# USBPowerWallSocket.net
KiCad netlist of a schematic drawn in EAGLE
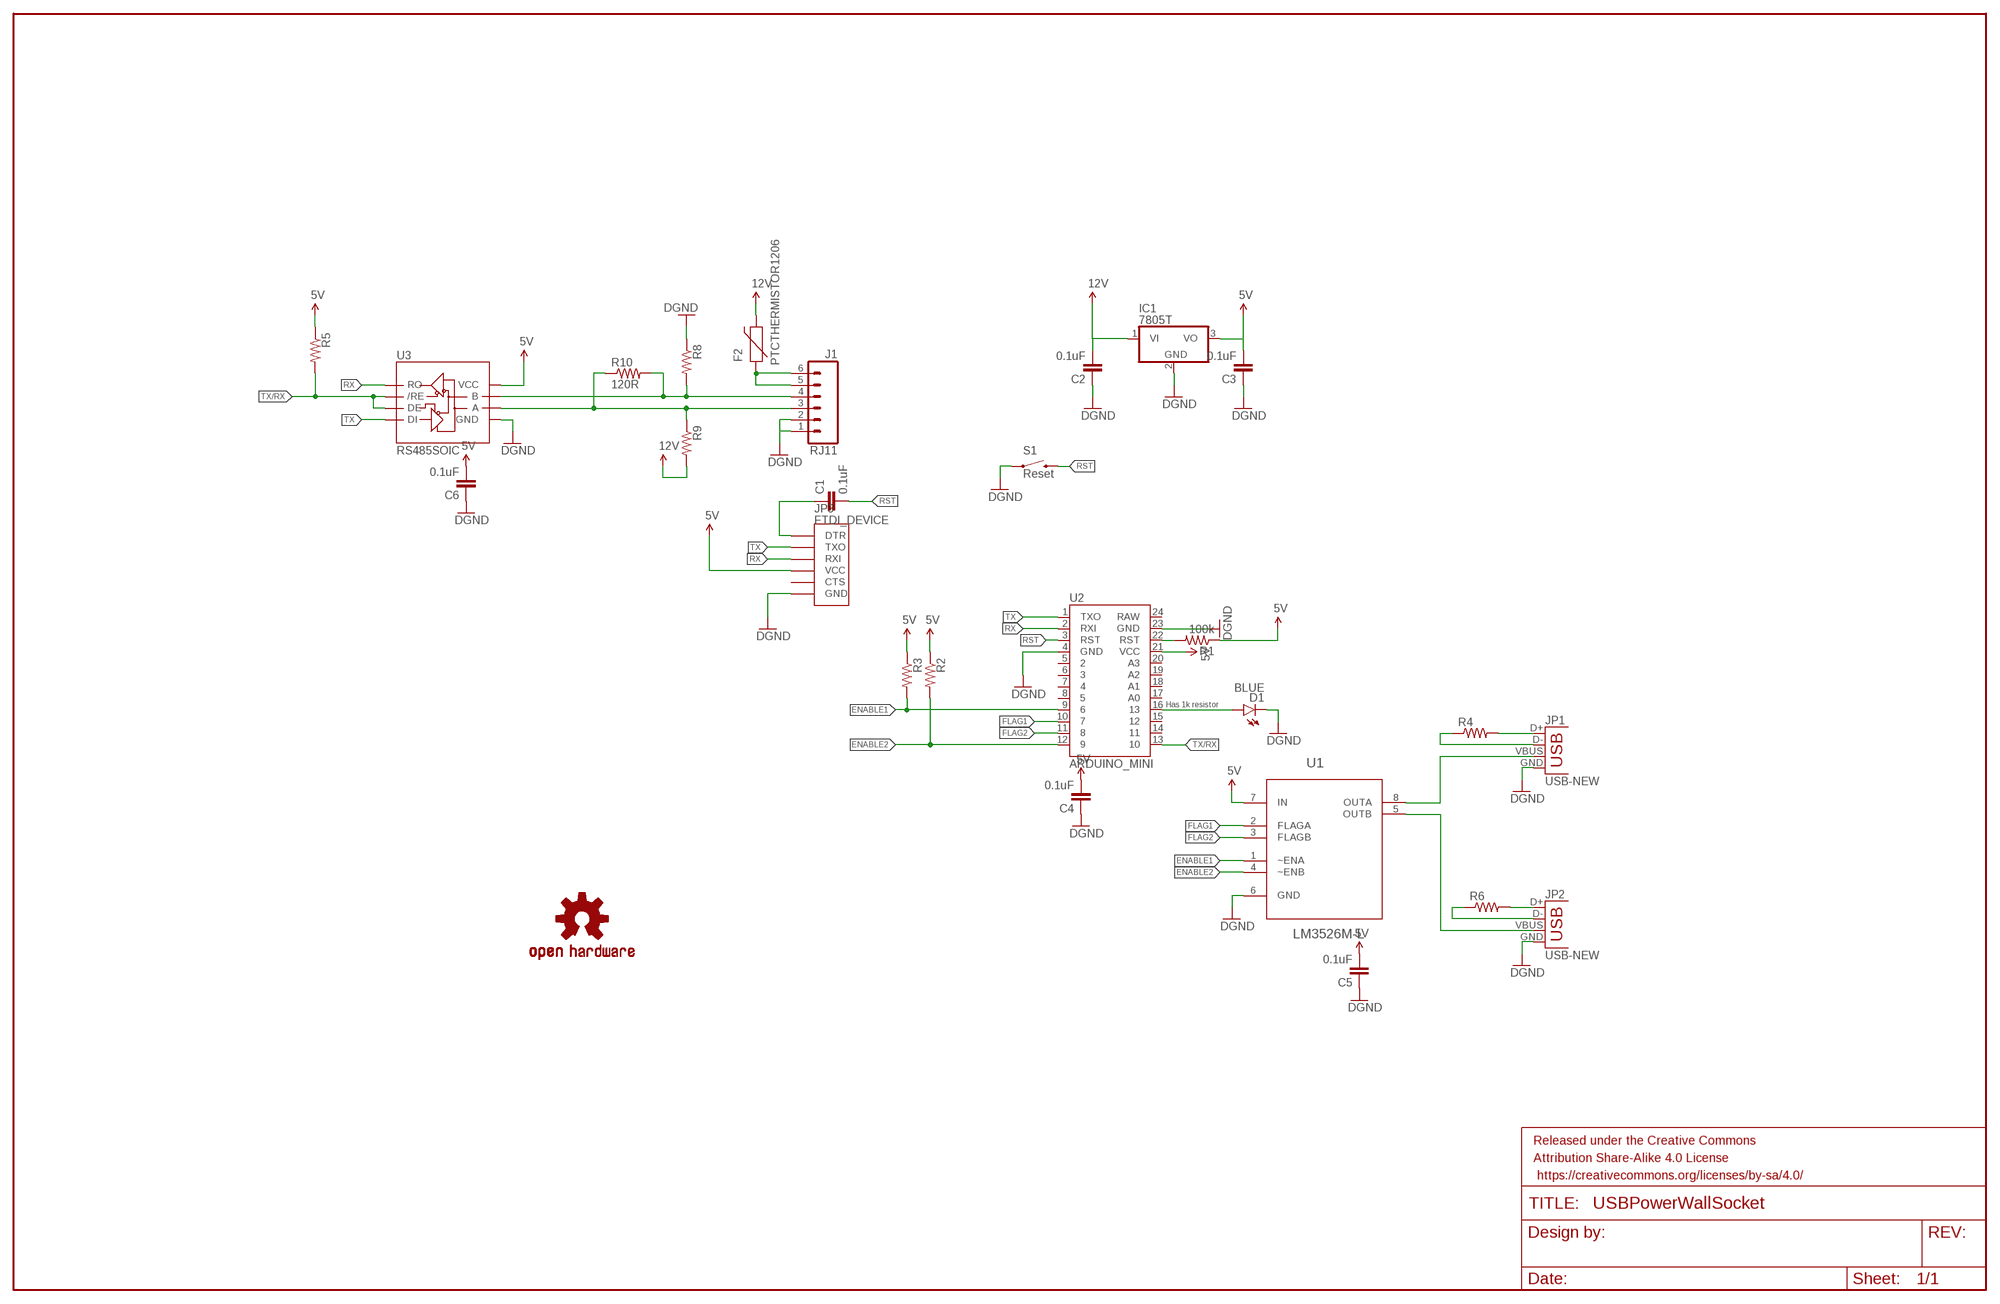
[diagram p0: schematic, sheet 1]

(export (version "E")
  (design (tool "Eeschema 10.0.6"))
  (components
    (comp (ref "C1")
      (value "0.1uF")
      (footprint "eagle-import:0805")
      (libsource (lib "eagle-import") (part "CAP0805"))
    )
    (comp (ref "C2")
      (value "0.1uF")
      (footprint "eagle-import:0805")
      (libsource (lib "eagle-import") (part "CAP0805"))
    )
    (comp (ref "C3")
      (value "0.1uF")
      (footprint "eagle-import:0805")
      (libsource (lib "eagle-import") (part "CAP0805"))
    )
    (comp (ref "C4")
      (value "0.1uF")
      (footprint "eagle-import:0805")
      (libsource (lib "eagle-import") (part "CAP0805"))
    )
    (comp (ref "C5")
      (value "0.1uF")
      (footprint "eagle-import:0805")
      (libsource (lib "eagle-import") (part "CAP0805"))
    )
    (comp (ref "C6")
      (value "0.1uF")
      (footprint "eagle-import:0805")
      (libsource (lib "eagle-import") (part "CAP0805"))
    )
    (comp (ref "D1")
      (value "BLUE")
      (footprint "eagle-import:LED-1206")
      (libsource (lib "eagle-import") (part "LED-BLUE1206"))
    )
    (comp (ref "F2")
      (value "PTCTHERMISTOR1206")
      (footprint "eagle-import:PTC-1206")
      (libsource (lib "eagle-import") (part "PTCTHERMISTOR1206"))
    )
    (comp (ref "FRAME1")
      (value "FRAME-LEDGER")
      (footprint "eagle-import:CREATIVE_COMMONS")
      (libsource (lib "eagle-import") (part "FRAME-LEDGER"))
    )
    (comp (ref "IC1")
      (value "7805T")
      (footprint "eagle-import:TO220H")
      (libsource (lib "eagle-import") (part "78T05"))
    )
    (comp (ref "J1")
      (value "RJ11")
      (footprint "eagle-import:RJ11-6")
      (libsource (lib "eagle-import") (part "RJ11-6PTH"))
    )
    (comp (ref "JP1")
      (value "USB-NEW")
      (footprint "eagle-import:USB-A-VERTICAL")
      (libsource (lib "eagle-import") (part "USB-NEW"))
    )
    (comp (ref "JP2")
      (value "USB-NEW")
      (footprint "eagle-import:USB-A-VERTICAL")
      (libsource (lib "eagle-import") (part "USB-NEW"))
    )
    (comp (ref "JP3")
      (value "FTDI_DEVICE")
      (footprint "eagle-import:FTDI_DEVICE_SIDE")
      (libsource (lib "eagle-import") (part "FTDI_DEVICE"))
    )
    (comp (ref "LOGO1")
      (value "OSHW-LOGOM")
      (footprint "eagle-import:OSHW-LOGO-M")
      (libsource (lib "eagle-import") (part "OSHW-LOGOM"))
    )
    (comp (ref "R1")
      (value "100k")
      (footprint "eagle-import:0805")
      (libsource (lib "eagle-import") (part "RESISTOR0805-RES"))
    )
    (comp (ref "R2")
      (value "RESISTOR0805-RES")
      (footprint "eagle-import:0805")
      (libsource (lib "eagle-import") (part "RESISTOR0805-RES"))
    )
    (comp (ref "R3")
      (value "RESISTOR0805-RES")
      (footprint "eagle-import:0805")
      (libsource (lib "eagle-import") (part "RESISTOR0805-RES"))
    )
    (comp (ref "R4")
      (value "RESISTOR0805-RES")
      (footprint "eagle-import:0805")
      (libsource (lib "eagle-import") (part "RESISTOR0805-RES"))
    )
    (comp (ref "R5")
      (value "RESISTOR0805-RES")
      (footprint "eagle-import:0805")
      (libsource (lib "eagle-import") (part "RESISTOR0805-RES"))
    )
    (comp (ref "R6")
      (value "RESISTOR0805-RES")
      (footprint "eagle-import:0805")
      (libsource (lib "eagle-import") (part "RESISTOR0805-RES"))
    )
    (comp (ref "R8")
      (value "RESISTOR0805-RES")
      (footprint "eagle-import:0805")
      (libsource (lib "eagle-import") (part "RESISTOR0805-RES"))
    )
    (comp (ref "R9")
      (value "RESISTOR0805-RES")
      (footprint "eagle-import:0805")
      (libsource (lib "eagle-import") (part "RESISTOR0805-RES"))
    )
    (comp (ref "R10")
      (value "120R")
      (footprint "eagle-import:0805")
      (libsource (lib "eagle-import") (part "RESISTOR0805-RES"))
    )
    (comp (ref "S1")
      (value "Reset")
      (footprint "eagle-import:TACTILE-PTH")
      (libsource (lib "eagle-import") (part "SWITCH-MOMENTARY-2PTH"))
    )
    (comp (ref "U1")
      (value "LM3526M-L")
      (footprint "eagle-import:SOIC127P640X175-8N")
      (libsource (lib "eagle-import") (part "LM3526M-L"))
    )
    (comp (ref "U2")
      (value "ARDUINO_MINI")
      (footprint "eagle-import:ARDUINO_MINI")
      (libsource (lib "eagle-import") (part "ARDUINO_MINI"))
    )
    (comp (ref "U3")
      (value "RS485SOIC")
      (footprint "eagle-import:SO08")
      (libsource (lib "eagle-import") (part "RS485SOIC"))
    )
  )
  (nets
    (net (code "1") (name "5V") (class "Default")
      (node (ref "C3") (pin "2") (pinfunction "2_2") (pintype "passive"))
      (node (ref "C4") (pin "2") (pinfunction "2_2") (pintype "passive"))
      (node (ref "C5") (pin "2") (pinfunction "2_2") (pintype "passive"))
      (node (ref "C6") (pin "2") (pinfunction "2_2") (pintype "passive"))
      (node (ref "IC1") (pin "3") (pinfunction "VO_3") (pintype "passive"))
      (node (ref "JP3") (pin "P$4") (pinfunction "VCC_P$4") (pintype "bidirectional"))
      (node (ref "R1") (pin "1") (pinfunction "1_1") (pintype "passive"))
      (node (ref "R2") (pin "1") (pinfunction "1_1") (pintype "passive"))
      (node (ref "R3") (pin "1") (pinfunction "1_1") (pintype "passive"))
      (node (ref "R5") (pin "1") (pinfunction "1_1") (pintype "passive"))
      (node (ref "U1") (pin "7") (pinfunction "IN_7") (pintype "power_in"))
      (node (ref "U2") (pin "21") (pinfunction "VCC_21") (pintype "bidirectional"))
      (node (ref "U3") (pin "8") (pinfunction "VCC_8") (pintype "bidirectional"))
    )
    (net (code "2") (name "12V") (class "Default")
      (node (ref "C2") (pin "2") (pinfunction "2_2") (pintype "passive"))
      (node (ref "F2") (pin "2") (pinfunction "2_2") (pintype "bidirectional"))
      (node (ref "IC1") (pin "1") (pinfunction "VI_1") (pintype "input"))
      (node (ref "R9") (pin "2") (pinfunction "2_2") (pintype "passive"))
    )
    (net (code "3") (name "DGND") (class "Default")
      (node (ref "C2") (pin "1") (pinfunction "1_1") (pintype "passive"))
      (node (ref "C3") (pin "1") (pinfunction "1_1") (pintype "passive"))
      (node (ref "C4") (pin "1") (pinfunction "1_1") (pintype "passive"))
      (node (ref "C5") (pin "1") (pinfunction "1_1") (pintype "passive"))
      (node (ref "C6") (pin "1") (pinfunction "1_1") (pintype "passive"))
      (node (ref "D1") (pin "C") (pinfunction "C_C") (pintype "passive"))
      (node (ref "IC1") (pin "2") (pinfunction "GND_2") (pintype "passive"))
      (node (ref "J1") (pin "1") (pinfunction "1_1") (pintype "passive"))
      (node (ref "J1") (pin "2") (pinfunction "2_2") (pintype "passive"))
      (node (ref "JP1") (pin "GND") (pinfunction "GND_GND") (pintype "bidirectional"))
      (node (ref "JP2") (pin "GND") (pinfunction "GND_GND") (pintype "bidirectional"))
      (node (ref "JP3") (pin "P$6") (pinfunction "GND_P$6") (pintype "bidirectional"))
      (node (ref "R8") (pin "1") (pinfunction "1_1") (pintype "passive"))
      (node (ref "S1") (pin "1") (pinfunction "1_1") (pintype "passive"))
      (node (ref "U1") (pin "6") (pinfunction "GND_6") (pintype "passive"))
      (node (ref "U2") (pin "23") (pinfunction "GND_23") (pintype "bidirectional"))
      (node (ref "U2") (pin "4") (pinfunction "GND_4") (pintype "bidirectional"))
      (node (ref "U3") (pin "5") (pinfunction "GND_5") (pintype "bidirectional"))
    )
    (net (code "4") (name "ENABLE1") (class "Default")
      (node (ref "R3") (pin "2") (pinfunction "2_2") (pintype "passive"))
      (node (ref "U1") (pin "1") (pinfunction "~{ENA}_1") (pintype "input"))
      (node (ref "U2") (pin "9") (pinfunction "6_9") (pintype "bidirectional"))
    )
    (net (code "5") (name "ENABLE2") (class "Default")
      (node (ref "R2") (pin "2") (pinfunction "2_2") (pintype "passive"))
      (node (ref "U1") (pin "4") (pinfunction "~{ENB}_4") (pintype "input"))
      (node (ref "U2") (pin "12") (pinfunction "9_12") (pintype "bidirectional"))
    )
    (net (code "6") (name "FLAG1") (class "Default")
      (node (ref "U1") (pin "2") (pinfunction "FLAGA_2") (pintype "input"))
      (node (ref "U2") (pin "10") (pinfunction "7_10") (pintype "bidirectional"))
    )
    (net (code "7") (name "FLAG2") (class "Default")
      (node (ref "U1") (pin "3") (pinfunction "FLAGB_3") (pintype "input"))
      (node (ref "U2") (pin "11") (pinfunction "8_11") (pintype "bidirectional"))
    )
    (net (code "8") (name "Net-(F2-Pad1)") (class "Default")
      (node (ref "F2") (pin "1") (pinfunction "1_1") (pintype "bidirectional"))
      (node (ref "J1") (pin "5") (pinfunction "5_5") (pintype "passive"))
      (node (ref "J1") (pin "6") (pinfunction "6_6") (pintype "passive"))
    )
    (net (code "9") (name "Net-(JP1-PadD+)") (class "Default")
      (node (ref "JP1") (pin "D+") (pinfunction "D+_D+") (pintype "bidirectional"))
      (node (ref "R4") (pin "2") (pinfunction "2_2") (pintype "passive"))
    )
    (net (code "10") (name "Net-(JP1-PadD-)") (class "Default")
      (node (ref "JP1") (pin "D-") (pinfunction "D-_D-") (pintype "bidirectional"))
      (node (ref "R4") (pin "1") (pinfunction "1_1") (pintype "passive"))
    )
    (net (code "11") (name "Net-(JP2-PadD+)") (class "Default")
      (node (ref "JP2") (pin "D+") (pinfunction "D+_D+") (pintype "bidirectional"))
      (node (ref "R6") (pin "2") (pinfunction "2_2") (pintype "passive"))
    )
    (net (code "12") (name "Net-(JP2-PadD-)") (class "Default")
      (node (ref "JP2") (pin "D-") (pinfunction "D-_D-") (pintype "bidirectional"))
      (node (ref "R6") (pin "1") (pinfunction "1_1") (pintype "passive"))
    )
    (net (code "13") (name "Net-(JP3-DTR)") (class "Default")
      (node (ref "C1") (pin "1") (pinfunction "1_1") (pintype "passive"))
      (node (ref "JP3") (pin "P$1") (pinfunction "DTR_P$1") (pintype "bidirectional"))
    )
    (net (code "14") (name "Net-(R1-Pad2)") (class "Default")
      (node (ref "R1") (pin "2") (pinfunction "2_2") (pintype "passive"))
      (node (ref "U2") (pin "22") (pinfunction "RST_22") (pintype "bidirectional"))
    )
    (net (code "15") (name "Net-(U1-OUTA)") (class "Default")
      (node (ref "JP1") (pin "VBUS") (pinfunction "VBUS_VBUS") (pintype "bidirectional"))
      (node (ref "U1") (pin "8") (pinfunction "OUTA_8") (pintype "output"))
    )
    (net (code "16") (name "Net-(U1-OUTB)") (class "Default")
      (node (ref "JP2") (pin "VBUS") (pinfunction "VBUS_VBUS") (pintype "bidirectional"))
      (node (ref "U1") (pin "5") (pinfunction "OUTB_5") (pintype "output"))
    )
    (net (code "17") (name "Net-(U2-13)") (class "Default")
      (node (ref "D1") (pin "A") (pinfunction "A_A") (pintype "passive"))
      (node (ref "U2") (pin "16") (pinfunction "13_16") (pintype "bidirectional"))
    )
    (net (code "18") (name "Net-(U3-A)") (class "Default")
      (node (ref "J1") (pin "3") (pinfunction "3_3") (pintype "passive"))
      (node (ref "R10") (pin "1") (pinfunction "1_1") (pintype "passive"))
      (node (ref "R9") (pin "1") (pinfunction "1_1") (pintype "passive"))
      (node (ref "U3") (pin "6") (pinfunction "A_6") (pintype "bidirectional"))
    )
    (net (code "19") (name "Net-(U3-B)") (class "Default")
      (node (ref "J1") (pin "4") (pinfunction "4_4") (pintype "passive"))
      (node (ref "R10") (pin "2") (pinfunction "2_2") (pintype "passive"))
      (node (ref "R8") (pin "2") (pinfunction "2_2") (pintype "passive"))
      (node (ref "U3") (pin "7") (pinfunction "B_7") (pintype "bidirectional"))
    )
    (net (code "20") (name "RST") (class "Default")
      (node (ref "C1") (pin "2") (pinfunction "2_2") (pintype "passive"))
      (node (ref "S1") (pin "3") (pinfunction "2_3") (pintype "passive"))
      (node (ref "U2") (pin "3") (pinfunction "RST_3") (pintype "bidirectional"))
    )
    (net (code "21") (name "RX") (class "Default")
      (node (ref "JP3") (pin "P$3") (pinfunction "RXI_P$3") (pintype "bidirectional"))
      (node (ref "U2") (pin "2") (pinfunction "RXI_2") (pintype "bidirectional"))
      (node (ref "U3") (pin "1") (pinfunction "RO_1") (pintype "bidirectional"))
    )
    (net (code "22") (name "TX") (class "Default")
      (node (ref "JP3") (pin "P$2") (pinfunction "TXO_P$2") (pintype "bidirectional"))
      (node (ref "U2") (pin "1") (pinfunction "TXO_1") (pintype "bidirectional"))
      (node (ref "U3") (pin "4") (pinfunction "DI_4") (pintype "bidirectional"))
    )
    (net (code "23") (name "TX{slash}RX") (class "Default")
      (node (ref "R5") (pin "2") (pinfunction "2_2") (pintype "passive"))
      (node (ref "U2") (pin "13") (pinfunction "10_13") (pintype "bidirectional"))
      (node (ref "U3") (pin "2") (pinfunction "/RE_2") (pintype "bidirectional"))
      (node (ref "U3") (pin "3") (pinfunction "DE_3") (pintype "bidirectional"))
    )
    (net (code "24") (name "unconnected-(JP3-CTS-PadP$5)") (class "Default")
      (node (ref "JP3") (pin "P$5") (pinfunction "CTS_P$5") (pintype "bidirectional"))
    )
    (net (code "25") (name "unconnected-(U2-2-Pad5)") (class "Default")
      (node (ref "U2") (pin "5") (pinfunction "2_5") (pintype "bidirectional"))
    )
    (net (code "26") (name "unconnected-(U2-3-Pad6)") (class "Default")
      (node (ref "U2") (pin "6") (pinfunction "3_6") (pintype "bidirectional"))
    )
    (net (code "27") (name "unconnected-(U2-4-Pad7)") (class "Default")
      (node (ref "U2") (pin "7") (pinfunction "4_7") (pintype "bidirectional"))
    )
    (net (code "28") (name "unconnected-(U2-5-Pad8)") (class "Default")
      (node (ref "U2") (pin "8") (pinfunction "5_8") (pintype "bidirectional"))
    )
    (net (code "29") (name "unconnected-(U2-11-Pad14)") (class "Default")
      (node (ref "U2") (pin "14") (pinfunction "11_14") (pintype "bidirectional"))
    )
    (net (code "30") (name "unconnected-(U2-12-Pad15)") (class "Default")
      (node (ref "U2") (pin "15") (pinfunction "12_15") (pintype "bidirectional"))
    )
    (net (code "31") (name "unconnected-(U2-A0-Pad17)") (class "Default")
      (node (ref "U2") (pin "17") (pinfunction "A0_17") (pintype "bidirectional"))
    )
    (net (code "32") (name "unconnected-(U2-A1-Pad18)") (class "Default")
      (node (ref "U2") (pin "18") (pinfunction "A1_18") (pintype "bidirectional"))
    )
    (net (code "33") (name "unconnected-(U2-A2-Pad19)") (class "Default")
      (node (ref "U2") (pin "19") (pinfunction "A2_19") (pintype "bidirectional"))
    )
    (net (code "34") (name "unconnected-(U2-A3-Pad20)") (class "Default")
      (node (ref "U2") (pin "20") (pinfunction "A3_20") (pintype "bidirectional"))
    )
    (net (code "35") (name "unconnected-(U2-RAW-Pad24)") (class "Default")
      (node (ref "U2") (pin "24") (pinfunction "RAW_24") (pintype "bidirectional"))
    )
  )
)
